# meld_fb2.net
KiCad netlist of a schematic drawn in EAGLE
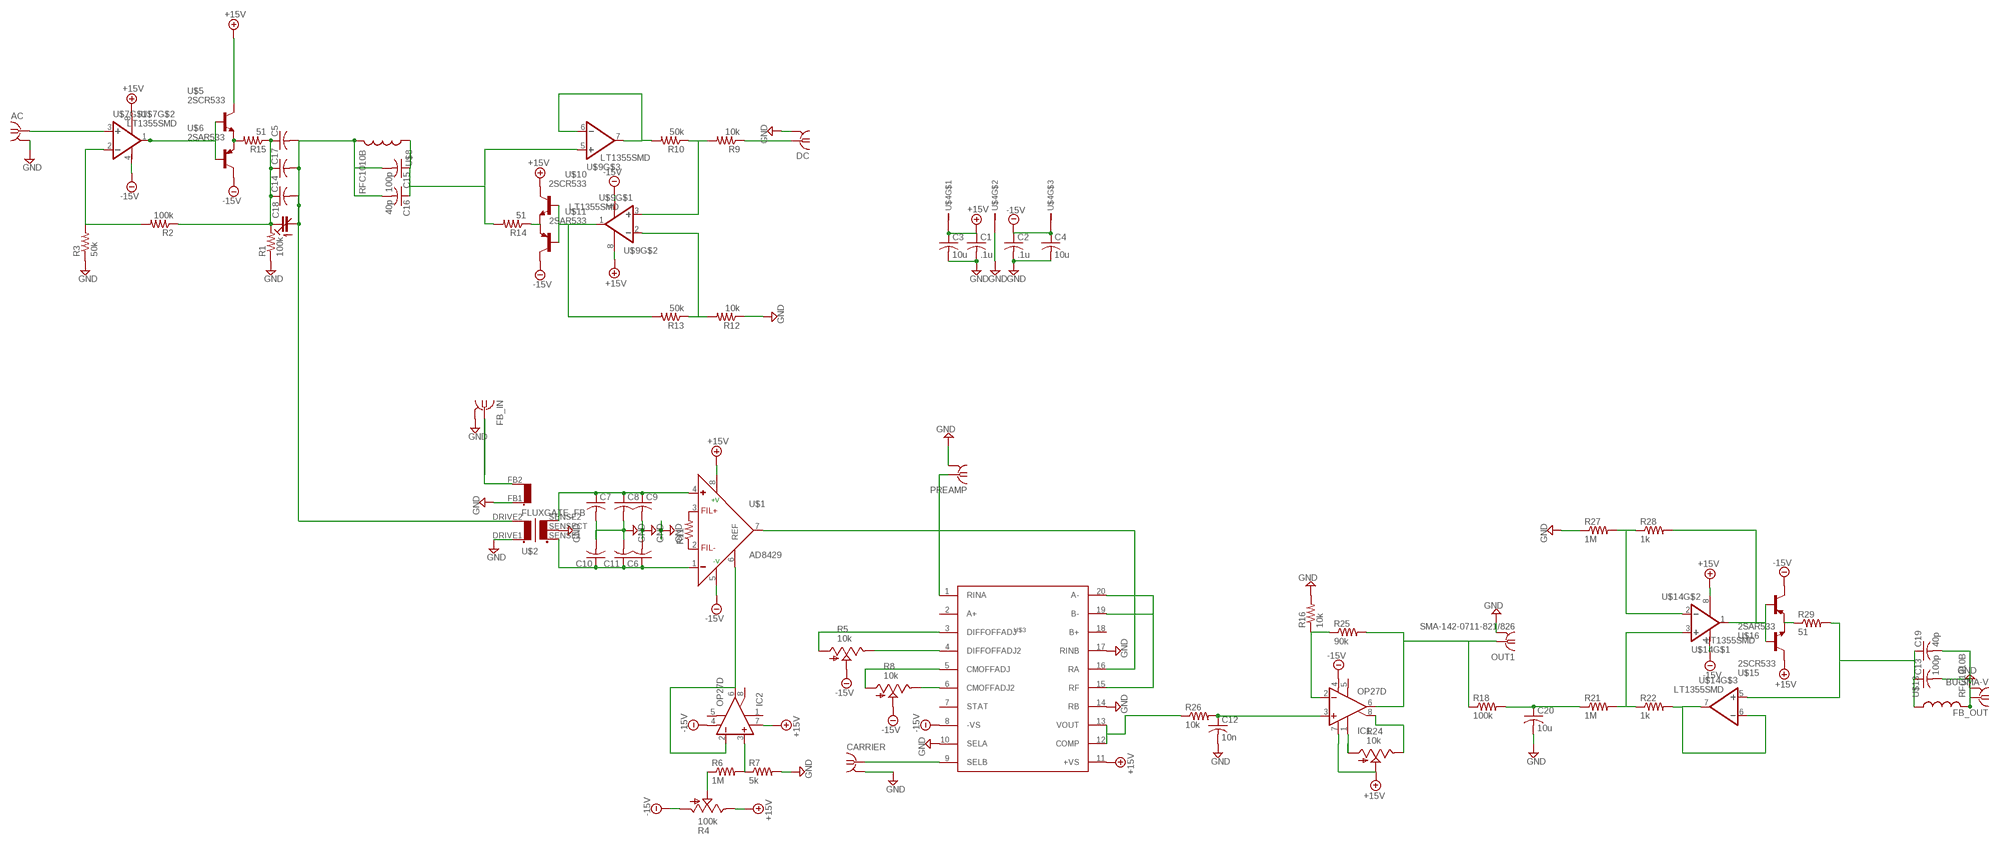
[diagram p0: schematic, sheet 1]

(export (version "E")
  (design (tool "Eeschema 10.0.6"))
  (components
    (comp (ref "AC")
      (value "SMA-142-0711-821/826")
      (footprint "eagle-import:J502-ND-142-0711-821_826")
      (fields (field (name "MF") "JOHNSON COMPONENTS") (field (name "MPN") "142-0711-821"))
      (libsource (lib "eagle-import") (part "SMA-142-0711-821/826"))
    )
    (comp (ref "C1")
      (value ".1u")
      (footprint "eagle-import:C1206")
      (libsource (lib "eagle-import") (part "C-USC1206"))
    )
    (comp (ref "C2")
      (value ".1u")
      (footprint "eagle-import:C1206")
      (libsource (lib "eagle-import") (part "C-USC1206"))
    )
    (comp (ref "C3")
      (value "10u")
      (footprint "eagle-import:C1206")
      (libsource (lib "eagle-import") (part "C-USC1206"))
    )
    (comp (ref "C4")
      (value "10u")
      (footprint "eagle-import:C1206")
      (libsource (lib "eagle-import") (part "C-USC1206"))
    )
    (comp (ref "C5")
      (value "C-USC0805")
      (footprint "eagle-import:C0805")
      (libsource (lib "eagle-import") (part "C-USC0805"))
    )
    (comp (ref "C6")
      (value "C-USC0805")
      (footprint "eagle-import:C0805")
      (libsource (lib "eagle-import") (part "C-USC0805"))
    )
    (comp (ref "C7")
      (value "C-USC0805")
      (footprint "eagle-import:C0805")
      (libsource (lib "eagle-import") (part "C-USC0805"))
    )
    (comp (ref "C8")
      (value "C-USC0805")
      (footprint "eagle-import:C0805")
      (libsource (lib "eagle-import") (part "C-USC0805"))
    )
    (comp (ref "C9")
      (value "C-USC0805")
      (footprint "eagle-import:C0805")
      (libsource (lib "eagle-import") (part "C-USC0805"))
    )
    (comp (ref "C10")
      (value "C-USC0805")
      (footprint "eagle-import:C0805")
      (libsource (lib "eagle-import") (part "C-USC0805"))
    )
    (comp (ref "C11")
      (value "C-USC0805")
      (footprint "eagle-import:C0805")
      (libsource (lib "eagle-import") (part "C-USC0805"))
    )
    (comp (ref "C12")
      (value "10n")
      (footprint "eagle-import:C0805")
      (libsource (lib "eagle-import") (part "C-USC0805"))
    )
    (comp (ref "C13")
      (value "100p")
      (footprint "eagle-import:C0805")
      (libsource (lib "eagle-import") (part "C-USC0805"))
    )
    (comp (ref "C14")
      (value "C-USC0805")
      (footprint "eagle-import:C0805")
      (libsource (lib "eagle-import") (part "C-USC0805"))
    )
    (comp (ref "C15")
      (value "100p")
      (footprint "eagle-import:C0805")
      (libsource (lib "eagle-import") (part "C-USC0805"))
    )
    (comp (ref "C16")
      (value "40p")
      (footprint "eagle-import:C0805")
      (libsource (lib "eagle-import") (part "C-USC0805"))
    )
    (comp (ref "C17")
      (value "C-USC0805")
      (footprint "eagle-import:C0805")
      (libsource (lib "eagle-import") (part "C-USC0805"))
    )
    (comp (ref "C18")
      (value "C-TRIMM")
      (footprint "eagle-import:SGC3S")
      (libsource (lib "eagle-import") (part "C-TRIMM"))
    )
    (comp (ref "C19")
      (value "40p")
      (footprint "eagle-import:C0805")
      (libsource (lib "eagle-import") (part "C-USC0805"))
    )
    (comp (ref "C20")
      (value "10u")
      (footprint "eagle-import:C1206")
      (libsource (lib "eagle-import") (part "C-USC1206"))
    )
    (comp (ref "CARRIER")
      (value "SMA-142-0711-821/826")
      (footprint "eagle-import:J502-ND-142-0711-821_826")
      (fields (field (name "MF") "JOHNSON COMPONENTS") (field (name "MPN") "142-0711-821"))
      (libsource (lib "eagle-import") (part "SMA-142-0711-821/826"))
    )
    (comp (ref "DC")
      (value "SMA-142-0711-821/826")
      (footprint "eagle-import:J502-ND-142-0711-821_826")
      (fields (field (name "MF") "JOHNSON COMPONENTS") (field (name "MPN") "142-0711-821"))
      (libsource (lib "eagle-import") (part "SMA-142-0711-821/826"))
    )
    (comp (ref "FB_IN")
      (value "SMA-142-0711-821/826")
      (footprint "eagle-import:J502-ND-142-0711-821_826")
      (fields (field (name "MF") "JOHNSON COMPONENTS") (field (name "MPN") "142-0711-821"))
      (libsource (lib "eagle-import") (part "SMA-142-0711-821/826"))
    )
    (comp (ref "FB_OUT")
      (value "BU-SMA-V")
      (footprint "eagle-import:BU-SMA-V")
      (libsource (lib "eagle-import") (part "BU-SMA-V"))
    )
    (comp (ref "IC1")
      (value "OP27D")
      (footprint "eagle-import:SO08")
      (libsource (lib "eagle-import") (part "OP27D"))
    )
    (comp (ref "IC2")
      (value "OP27D")
      (footprint "eagle-import:SO08")
      (libsource (lib "eagle-import") (part "OP27D"))
    )
    (comp (ref "OUT1")
      (value "SMA-142-0711-821/826")
      (footprint "eagle-import:J502-ND-142-0711-821_826")
      (fields (field (name "MF") "JOHNSON COMPONENTS") (field (name "MPN") "142-0711-821"))
      (libsource (lib "eagle-import") (part "SMA-142-0711-821/826"))
    )
    (comp (ref "PREAMP")
      (value "SMA-142-0711-821/826")
      (footprint "eagle-import:J502-ND-142-0711-821_826")
      (fields (field (name "MF") "JOHNSON COMPONENTS") (field (name "MPN") "142-0711-821"))
      (libsource (lib "eagle-import") (part "SMA-142-0711-821/826"))
    )
    (comp (ref "R1")
      (value "100k")
      (footprint "eagle-import:R0805")
      (libsource (lib "eagle-import") (part "R-US_R0805"))
    )
    (comp (ref "R2")
      (value "100k")
      (footprint "eagle-import:R0805")
      (libsource (lib "eagle-import") (part "R-US_R0805"))
    )
    (comp (ref "R3")
      (value "50k")
      (footprint "eagle-import:R0805")
      (libsource (lib "eagle-import") (part "R-US_R0805"))
    )
    (comp (ref "R4")
      (value "100k")
      (footprint "eagle-import:B64Y")
      (libsource (lib "eagle-import") (part "TRIM_US-B64Y"))
    )
    (comp (ref "R5")
      (value "10k")
      (footprint "eagle-import:B64Y")
      (libsource (lib "eagle-import") (part "TRIM_US-B64Y"))
    )
    (comp (ref "R6")
      (value "1M")
      (footprint "eagle-import:R0805")
      (libsource (lib "eagle-import") (part "R-US_R0805"))
    )
    (comp (ref "R7")
      (value "5k")
      (footprint "eagle-import:R0805")
      (libsource (lib "eagle-import") (part "R-US_R0805"))
    )
    (comp (ref "R8")
      (value "10k")
      (footprint "eagle-import:B64Y")
      (libsource (lib "eagle-import") (part "TRIM_US-B64Y"))
    )
    (comp (ref "R9")
      (value "10k")
      (footprint "eagle-import:R0805")
      (libsource (lib "eagle-import") (part "R-US_R0805"))
    )
    (comp (ref "R10")
      (value "50k")
      (footprint "eagle-import:R0805")
      (libsource (lib "eagle-import") (part "R-US_R0805"))
    )
    (comp (ref "R11")
      (value "R-US_R0805")
      (footprint "eagle-import:R0805")
      (libsource (lib "eagle-import") (part "R-US_R0805"))
    )
    (comp (ref "R12")
      (value "10k")
      (footprint "eagle-import:R0805")
      (libsource (lib "eagle-import") (part "R-US_R0805"))
    )
    (comp (ref "R13")
      (value "50k")
      (footprint "eagle-import:R0805")
      (libsource (lib "eagle-import") (part "R-US_R0805"))
    )
    (comp (ref "R14")
      (value "51")
      (footprint "eagle-import:R2512")
      (libsource (lib "eagle-import") (part "R-US_R2512"))
    )
    (comp (ref "R15")
      (value "51")
      (footprint "eagle-import:R2512")
      (libsource (lib "eagle-import") (part "R-US_R2512"))
    )
    (comp (ref "R16")
      (value "10k")
      (footprint "eagle-import:R0805")
      (libsource (lib "eagle-import") (part "resistor_R-US_R0805"))
    )
    (comp (ref "R18")
      (value "100k")
      (footprint "eagle-import:R0805")
      (libsource (lib "eagle-import") (part "resistor_R-US_R0805"))
    )
    (comp (ref "R21")
      (value "1M")
      (footprint "eagle-import:R0805")
      (libsource (lib "eagle-import") (part "R-US_R0805"))
    )
    (comp (ref "R22")
      (value "1k")
      (footprint "eagle-import:R0805")
      (libsource (lib "eagle-import") (part "R-US_R0805"))
    )
    (comp (ref "R24")
      (value "10k")
      (footprint "eagle-import:B64Y")
      (libsource (lib "eagle-import") (part "TRIM_US-B64Y"))
    )
    (comp (ref "R25")
      (value "90k")
      (footprint "eagle-import:R0805")
      (libsource (lib "eagle-import") (part "resistor_R-US_R0805"))
    )
    (comp (ref "R26")
      (value "10k")
      (footprint "eagle-import:R0805")
      (libsource (lib "eagle-import") (part "resistor_R-US_R0805"))
    )
    (comp (ref "R27")
      (value "1M")
      (footprint "eagle-import:R0805")
      (libsource (lib "eagle-import") (part "R-US_R0805"))
    )
    (comp (ref "R28")
      (value "1k")
      (footprint "eagle-import:R0805")
      (libsource (lib "eagle-import") (part "R-US_R0805"))
    )
    (comp (ref "R29")
      (value "51")
      (footprint "eagle-import:R2512")
      (libsource (lib "eagle-import") (part "R-US_R2512"))
    )
    (comp (ref "U$1")
      (value "AD8429")
      (footprint "eagle-import:SO8")
      (libsource (lib "eagle-import") (part "AD8428"))
    )
    (comp (ref "U$2")
      (value "FLUXGATE_FB")
      (footprint "eagle-import:PARA_FB")
      (libsource (lib "eagle-import") (part "FLUXGATE_FB"))
    )
    (comp (ref "U$3")
      (value "AD630")
      (footprint "eagle-import:SOIC20R")
      (libsource (lib "eagle-import") (part "AD630"))
    )
    (comp (ref "U$4")
      (value "B3B-AM")
      (footprint "eagle-import:B3B-AM")
      (libsource (lib "eagle-import") (part "B3B-AM"))
    )
    (comp (ref "U$5")
      (value "2SCR533")
      (footprint "eagle-import:SOT89-BCE")
      (libsource (lib "eagle-import") (part "2SCR533"))
    )
    (comp (ref "U$6")
      (value "2SAR533")
      (footprint "eagle-import:SOT89-BCE")
      (libsource (lib "eagle-import") (part "2SAR533"))
    )
    (comp (ref "U$7")
      (value "LT1355SMD")
      (footprint "eagle-import:SOIC8")
      (libsource (lib "eagle-import") (part "LT1355SMD"))
    )
    (comp (ref "U$8")
      (value "RFC1010B")
      (footprint "eagle-import:186KE")
      (libsource (lib "eagle-import") (part "RFC1010B"))
    )
    (comp (ref "U$9")
      (value "LT1355SMD")
      (footprint "eagle-import:SOIC8")
      (libsource (lib "eagle-import") (part "LT1355SMD"))
    )
    (comp (ref "U$10")
      (value "2SCR533")
      (footprint "eagle-import:SOT89-BCE")
      (libsource (lib "eagle-import") (part "2SCR533"))
    )
    (comp (ref "U$11")
      (value "2SAR533")
      (footprint "eagle-import:SOT89-BCE")
      (libsource (lib "eagle-import") (part "2SAR533"))
    )
    (comp (ref "U$13")
      (value "RFC1010B")
      (footprint "eagle-import:186KE")
      (libsource (lib "eagle-import") (part "RFC1010B"))
    )
    (comp (ref "U$14")
      (value "LT1355SMD")
      (footprint "eagle-import:SOIC8")
      (libsource (lib "eagle-import") (part "LT1355SMD"))
    )
    (comp (ref "U$15")
      (value "2SCR533")
      (footprint "eagle-import:SOT89-BCE")
      (libsource (lib "eagle-import") (part "2SCR533"))
    )
    (comp (ref "U$16")
      (value "2SAR533")
      (footprint "eagle-import:SOT89-BCE")
      (libsource (lib "eagle-import") (part "2SAR533"))
    )
  )
  (nets
    (net (code "1") (name "+15V") (class "Default")
      (node (ref "C1") (pin "1") (pinfunction "1_1") (pintype "passive"))
      (node (ref "C3") (pin "1") (pinfunction "1_1") (pintype "passive"))
      (node (ref "IC1") (pin "7") (pinfunction "V+_7") (pintype "power_in"))
      (node (ref "IC2") (pin "7") (pinfunction "V+_7") (pintype "power_in"))
      (node (ref "R24") (pin "S") (pinfunction "S_S") (pintype "passive"))
      (node (ref "R4") (pin "E") (pinfunction "E_E") (pintype "passive"))
      (node (ref "U$1") (pin "8") (pinfunction "+V_8") (pintype "power_in"))
      (node (ref "U$10") (pin "C") (pinfunction "C_C") (pintype "passive"))
      (node (ref "U$14") (pin "8") (pinfunction "V+_8") (pintype "power_in"))
      (node (ref "U$15") (pin "C") (pinfunction "C_C") (pintype "passive"))
      (node (ref "U$3") (pin "11") (pinfunction "+VS_11") (pintype "bidirectional"))
      (node (ref "U$4") (pin "1") (pinfunction "1_1") (pintype "passive"))
      (node (ref "U$5") (pin "C") (pinfunction "C_C") (pintype "passive"))
      (node (ref "U$7") (pin "8") (pinfunction "V+_8") (pintype "power_in"))
      (node (ref "U$9") (pin "8") (pinfunction "V+_8") (pintype "power_in"))
    )
    (net (code "2") (name "-15V") (class "Default")
      (node (ref "C2") (pin "1") (pinfunction "1_1") (pintype "passive"))
      (node (ref "C4") (pin "1") (pinfunction "1_1") (pintype "passive"))
      (node (ref "IC1") (pin "4") (pinfunction "V-_4") (pintype "power_in"))
      (node (ref "IC2") (pin "4") (pinfunction "V-_4") (pintype "power_in"))
      (node (ref "R4") (pin "A") (pinfunction "A_A") (pintype "passive"))
      (node (ref "R5") (pin "S") (pinfunction "S_S") (pintype "passive"))
      (node (ref "R8") (pin "S") (pinfunction "S_S") (pintype "passive"))
      (node (ref "U$1") (pin "5") (pinfunction "-V_5") (pintype "power_in"))
      (node (ref "U$11") (pin "C") (pinfunction "C_C") (pintype "passive"))
      (node (ref "U$14") (pin "4") (pinfunction "V-_4") (pintype "power_in"))
      (node (ref "U$16") (pin "C") (pinfunction "C_C") (pintype "passive"))
      (node (ref "U$3") (pin "8") (pinfunction "-VS_8") (pintype "bidirectional"))
      (node (ref "U$4") (pin "3") (pinfunction "1_3") (pintype "passive"))
      (node (ref "U$6") (pin "C") (pinfunction "C_C") (pintype "passive"))
      (node (ref "U$7") (pin "4") (pinfunction "V-_4") (pintype "power_in"))
      (node (ref "U$9") (pin "4") (pinfunction "V-_4") (pintype "power_in"))
    )
    (net (code "3") (name "GND") (class "Default")
      (node (ref "AC") (pin "G@1") (pinfunction "2_G@1") (pintype "passive"))
      (node (ref "AC") (pin "G@2") (pinfunction "2_G@2") (pintype "passive"))
      (node (ref "AC") (pin "G@3") (pinfunction "2_G@3") (pintype "passive"))
      (node (ref "AC") (pin "G@4") (pinfunction "2_G@4") (pintype "passive"))
      (node (ref "C1") (pin "2") (pinfunction "2_2") (pintype "passive"))
      (node (ref "C10") (pin "2") (pinfunction "2_2") (pintype "passive"))
      (node (ref "C11") (pin "2") (pinfunction "2_2") (pintype "passive"))
      (node (ref "C12") (pin "2") (pinfunction "2_2") (pintype "passive"))
      (node (ref "C2") (pin "2") (pinfunction "2_2") (pintype "passive"))
      (node (ref "C20") (pin "2") (pinfunction "2_2") (pintype "passive"))
      (node (ref "C3") (pin "2") (pinfunction "2_2") (pintype "passive"))
      (node (ref "C4") (pin "2") (pinfunction "2_2") (pintype "passive"))
      (node (ref "C6") (pin "2") (pinfunction "2_2") (pintype "passive"))
      (node (ref "C7") (pin "2") (pinfunction "2_2") (pintype "passive"))
      (node (ref "C8") (pin "2") (pinfunction "2_2") (pintype "passive"))
      (node (ref "C9") (pin "2") (pinfunction "2_2") (pintype "passive"))
      (node (ref "CARRIER") (pin "G@1") (pinfunction "2_G@1") (pintype "passive"))
      (node (ref "CARRIER") (pin "G@2") (pinfunction "2_G@2") (pintype "passive"))
      (node (ref "CARRIER") (pin "G@3") (pinfunction "2_G@3") (pintype "passive"))
      (node (ref "CARRIER") (pin "G@4") (pinfunction "2_G@4") (pintype "passive"))
      (node (ref "DC") (pin "G@1") (pinfunction "2_G@1") (pintype "passive"))
      (node (ref "DC") (pin "G@2") (pinfunction "2_G@2") (pintype "passive"))
      (node (ref "DC") (pin "G@3") (pinfunction "2_G@3") (pintype "passive"))
      (node (ref "DC") (pin "G@4") (pinfunction "2_G@4") (pintype "passive"))
      (node (ref "FB_IN") (pin "G@1") (pinfunction "2_G@1") (pintype "passive"))
      (node (ref "FB_IN") (pin "G@2") (pinfunction "2_G@2") (pintype "passive"))
      (node (ref "FB_IN") (pin "G@3") (pinfunction "2_G@3") (pintype "passive"))
      (node (ref "FB_IN") (pin "G@4") (pinfunction "2_G@4") (pintype "passive"))
      (node (ref "FB_OUT") (pin "2") (pinfunction "2_2") (pintype "passive"))
      (node (ref "FB_OUT") (pin "3") (pinfunction "2_3") (pintype "passive"))
      (node (ref "FB_OUT") (pin "4") (pinfunction "2_4") (pintype "passive"))
      (node (ref "FB_OUT") (pin "5") (pinfunction "2_5") (pintype "passive"))
      (node (ref "OUT1") (pin "G@1") (pinfunction "2_G@1") (pintype "passive"))
      (node (ref "OUT1") (pin "G@2") (pinfunction "2_G@2") (pintype "passive"))
      (node (ref "OUT1") (pin "G@3") (pinfunction "2_G@3") (pintype "passive"))
      (node (ref "OUT1") (pin "G@4") (pinfunction "2_G@4") (pintype "passive"))
      (node (ref "PREAMP") (pin "G@1") (pinfunction "2_G@1") (pintype "passive"))
      (node (ref "PREAMP") (pin "G@2") (pinfunction "2_G@2") (pintype "passive"))
      (node (ref "PREAMP") (pin "G@3") (pinfunction "2_G@3") (pintype "passive"))
      (node (ref "PREAMP") (pin "G@4") (pinfunction "2_G@4") (pintype "passive"))
      (node (ref "R1") (pin "1") (pinfunction "1_1") (pintype "passive"))
      (node (ref "R12") (pin "1") (pinfunction "1_1") (pintype "passive"))
      (node (ref "R16") (pin "2") (pinfunction "2_2") (pintype "passive"))
      (node (ref "R27") (pin "1") (pinfunction "1_1") (pintype "passive"))
      (node (ref "R3") (pin "1") (pinfunction "1_1") (pintype "passive"))
      (node (ref "R7") (pin "2") (pinfunction "2_2") (pintype "passive"))
      (node (ref "U$2") (pin "DRIVE1") (pinfunction "1_DRIVE1") (pintype "passive"))
      (node (ref "U$2") (pin "FB1") (pinfunction "6_FB1") (pintype "passive"))
      (node (ref "U$2") (pin "SENSECT") (pinfunction "4_SENSECT") (pintype "passive"))
      (node (ref "U$3") (pin "10") (pinfunction "SELA_10") (pintype "bidirectional"))
      (node (ref "U$3") (pin "14") (pinfunction "RB_14") (pintype "bidirectional"))
      (node (ref "U$3") (pin "17") (pinfunction "RINB_17") (pintype "bidirectional"))
      (node (ref "U$4") (pin "2") (pinfunction "1_2") (pintype "passive"))
    )
    (net (code "4") (name "Net-(C18-A)") (class "Default")
      (node (ref "C14") (pin "2") (pinfunction "2_2") (pintype "passive"))
      (node (ref "C15") (pin "2") (pinfunction "2_2") (pintype "passive"))
      (node (ref "C16") (pin "2") (pinfunction "2_2") (pintype "passive"))
      (node (ref "C17") (pin "2") (pinfunction "2_2") (pintype "passive"))
      (node (ref "C18") (pin "P$1") (pinfunction "A_P$1") (pintype "passive"))
      (node (ref "C5") (pin "2") (pinfunction "2_2") (pintype "passive"))
      (node (ref "U$2") (pin "DRIVE2") (pinfunction "2_DRIVE2") (pintype "passive"))
      (node (ref "U$8") (pin "P$2") (pinfunction "2_P$2") (pintype "passive"))
    )
    (net (code "5") (name "Net-(C18-E)") (class "Default")
      (node (ref "C14") (pin "1") (pinfunction "1_1") (pintype "passive"))
      (node (ref "C17") (pin "1") (pinfunction "1_1") (pintype "passive"))
      (node (ref "C18") (pin "P$2") (pinfunction "E_P$2") (pintype "passive"))
      (node (ref "C5") (pin "1") (pinfunction "1_1") (pintype "passive"))
      (node (ref "R1") (pin "2") (pinfunction "2_2") (pintype "passive"))
      (node (ref "R15") (pin "1") (pinfunction "1_1") (pintype "passive"))
      (node (ref "R2") (pin "1") (pinfunction "1_1") (pintype "passive"))
    )
    (net (code "6") (name "Net-(C20-Pad1)") (class "Default")
      (node (ref "C20") (pin "1") (pinfunction "1_1") (pintype "passive"))
      (node (ref "R18") (pin "2") (pinfunction "2_2") (pintype "passive"))
      (node (ref "R21") (pin "1") (pinfunction "1_1") (pintype "passive"))
    )
    (net (code "7") (name "Net-(DC-Pad1)") (class "Default")
      (node (ref "DC") (pin "1") (pinfunction "1_1") (pintype "passive"))
      (node (ref "R9") (pin "1") (pinfunction "1_1") (pintype "passive"))
    )
    (net (code "8") (name "Net-(IC1-+IN)") (class "Default")
      (node (ref "C12") (pin "1") (pinfunction "1_1") (pintype "passive"))
      (node (ref "IC1") (pin "3") (pinfunction "+IN_3") (pintype "input"))
      (node (ref "R26") (pin "2") (pinfunction "2_2") (pintype "passive"))
    )
    (net (code "9") (name "Net-(IC1--IN)") (class "Default")
      (node (ref "IC1") (pin "2") (pinfunction "-IN_2") (pintype "input"))
      (node (ref "R16") (pin "1") (pinfunction "1_1") (pintype "passive"))
      (node (ref "R25") (pin "1") (pinfunction "1_1") (pintype "passive"))
    )
    (net (code "10") (name "Net-(IC1-ON1)") (class "Default")
      (node (ref "IC1") (pin "1") (pinfunction "ON1_1") (pintype "passive"))
      (node (ref "R24") (pin "A") (pinfunction "A_A") (pintype "passive"))
    )
    (net (code "11") (name "Net-(IC1-ON2)") (class "Default")
      (node (ref "IC1") (pin "8") (pinfunction "ON2_8") (pintype "passive"))
      (node (ref "R24") (pin "E") (pinfunction "E_E") (pintype "passive"))
    )
    (net (code "12") (name "Net-(IC1-OUT)") (class "Default")
      (node (ref "IC1") (pin "6") (pinfunction "OUT_6") (pintype "output"))
      (node (ref "OUT1") (pin "1") (pinfunction "1_1") (pintype "passive"))
      (node (ref "R18") (pin "1") (pinfunction "1_1") (pintype "passive"))
      (node (ref "R25") (pin "2") (pinfunction "2_2") (pintype "passive"))
    )
    (net (code "13") (name "Net-(IC2-+IN)") (class "Default")
      (node (ref "IC2") (pin "3") (pinfunction "+IN_3") (pintype "input"))
      (node (ref "R6") (pin "2") (pinfunction "2_2") (pintype "passive"))
      (node (ref "R7") (pin "1") (pinfunction "1_1") (pintype "passive"))
    )
    (net (code "14") (name "Net-(IC2--IN)") (class "Default")
      (node (ref "IC2") (pin "2") (pinfunction "-IN_2") (pintype "input"))
      (node (ref "IC2") (pin "6") (pinfunction "OUT_6") (pintype "output"))
      (node (ref "U$1") (pin "6") (pinfunction "REF_6") (pintype "passive"))
    )
    (net (code "15") (name "Net-(R4-PadS)") (class "Default")
      (node (ref "R4") (pin "S") (pinfunction "S_S") (pintype "passive"))
      (node (ref "R6") (pin "1") (pinfunction "1_1") (pintype "passive"))
    )
    (net (code "16") (name "Net-(R14-Pad1)") (class "Default")
      (node (ref "R14") (pin "1") (pinfunction "1_1") (pintype "passive"))
      (node (ref "U$10") (pin "E") (pinfunction "E_E") (pintype "passive"))
      (node (ref "U$11") (pin "E") (pinfunction "E_E") (pintype "passive"))
    )
    (net (code "17") (name "Net-(R15-Pad2)") (class "Default")
      (node (ref "R15") (pin "2") (pinfunction "2_2") (pintype "passive"))
      (node (ref "U$5") (pin "E") (pinfunction "E_E") (pintype "passive"))
      (node (ref "U$6") (pin "E") (pinfunction "E_E") (pintype "passive"))
    )
    (net (code "18") (name "Net-(R29-Pad1)") (class "Default")
      (node (ref "R29") (pin "1") (pinfunction "1_1") (pintype "passive"))
      (node (ref "U$15") (pin "E") (pinfunction "E_E") (pintype "passive"))
      (node (ref "U$16") (pin "E") (pinfunction "E_E") (pintype "passive"))
    )
    (net (code "19") (name "Net-(U$1-+)") (class "Default")
      (node (ref "C7") (pin "1") (pinfunction "1_1") (pintype "passive"))
      (node (ref "C8") (pin "1") (pinfunction "1_1") (pintype "passive"))
      (node (ref "C9") (pin "1") (pinfunction "1_1") (pintype "passive"))
      (node (ref "U$1") (pin "4") (pinfunction "+_4") (pintype "input"))
      (node (ref "U$2") (pin "SENSE2") (pinfunction "3_SENSE2") (pintype "passive"))
    )
    (net (code "20") (name "Net-(U$1--)") (class "Default")
      (node (ref "C10") (pin "1") (pinfunction "1_1") (pintype "passive"))
      (node (ref "C11") (pin "1") (pinfunction "1_1") (pintype "passive"))
      (node (ref "C6") (pin "1") (pinfunction "1_1") (pintype "passive"))
      (node (ref "U$1") (pin "1") (pinfunction "-_1") (pintype "input"))
      (node (ref "U$2") (pin "SENSE1") (pinfunction "5_SENSE1") (pintype "passive"))
    )
    (net (code "21") (name "Net-(U$1-FIL+)") (class "Default")
      (node (ref "R11") (pin "2") (pinfunction "2_2") (pintype "passive"))
      (node (ref "U$1") (pin "3") (pinfunction "FIL+_3") (pintype "passive"))
    )
    (net (code "22") (name "Net-(U$1-FIL-)") (class "Default")
      (node (ref "R11") (pin "1") (pinfunction "1_1") (pintype "passive"))
      (node (ref "U$1") (pin "2") (pinfunction "FIL-_2") (pintype "passive"))
    )
    (net (code "23") (name "Net-(U$1-OUT)") (class "Default")
      (node (ref "PREAMP") (pin "1") (pinfunction "1_1") (pintype "passive"))
      (node (ref "U$1") (pin "7") (pinfunction "OUT_7") (pintype "output"))
      (node (ref "U$3") (pin "1") (pinfunction "RINA_1") (pintype "bidirectional"))
      (node (ref "U$3") (pin "16") (pinfunction "RA_16") (pintype "bidirectional"))
    )
    (net (code "24") (name "Net-(U$2-7)") (class "Default")
      (node (ref "FB_IN") (pin "1") (pinfunction "1_1") (pintype "passive"))
      (node (ref "U$2") (pin "FB2") (pinfunction "7_FB2") (pintype "passive"))
    )
    (net (code "25") (name "Net-(U$3-A-)") (class "Default")
      (node (ref "U$3") (pin "15") (pinfunction "RF_15") (pintype "bidirectional"))
      (node (ref "U$3") (pin "19") (pinfunction "B-_19") (pintype "bidirectional"))
      (node (ref "U$3") (pin "20") (pinfunction "A-_20") (pintype "bidirectional"))
    )
    (net (code "26") (name "Net-(U$3-CMOFFADJ)") (class "Default")
      (node (ref "R8") (pin "A") (pinfunction "A_A") (pintype "passive"))
      (node (ref "U$3") (pin "5") (pinfunction "CMOFFADJ_5") (pintype "bidirectional"))
    )
    (net (code "27") (name "Net-(U$3-CMOFFADJ2)") (class "Default")
      (node (ref "R8") (pin "E") (pinfunction "E_E") (pintype "passive"))
      (node (ref "U$3") (pin "6") (pinfunction "CMOFFADJ2_6") (pintype "bidirectional"))
    )
    (net (code "28") (name "Net-(U$3-COMP)") (class "Default")
      (node (ref "R26") (pin "1") (pinfunction "1_1") (pintype "passive"))
      (node (ref "U$3") (pin "12") (pinfunction "COMP_12") (pintype "bidirectional"))
      (node (ref "U$3") (pin "13") (pinfunction "VOUT_13") (pintype "bidirectional"))
    )
    (net (code "29") (name "Net-(U$3-DIFFOFFADJ)") (class "Default")
      (node (ref "R5") (pin "A") (pinfunction "A_A") (pintype "passive"))
      (node (ref "U$3") (pin "3") (pinfunction "DIFFOFFADJ_3") (pintype "bidirectional"))
    )
    (net (code "30") (name "Net-(U$3-DIFFOFFADJ2)") (class "Default")
      (node (ref "R5") (pin "E") (pinfunction "E_E") (pintype "passive"))
      (node (ref "U$3") (pin "4") (pinfunction "DIFFOFFADJ2_4") (pintype "bidirectional"))
    )
    (net (code "31") (name "Net-(U$3-SELB)") (class "Default")
      (node (ref "CARRIER") (pin "1") (pinfunction "1_1") (pintype "passive"))
      (node (ref "U$3") (pin "9") (pinfunction "SELB_9") (pintype "bidirectional"))
    )
    (net (code "32") (name "Net-(U$7A-+IN)") (class "Default")
      (node (ref "AC") (pin "1") (pinfunction "1_1") (pintype "passive"))
      (node (ref "U$7") (pin "3") (pinfunction "+IN_3") (pintype "input"))
    )
    (net (code "33") (name "Net-(U$7A--IN)") (class "Default")
      (node (ref "R2") (pin "2") (pinfunction "2_2") (pintype "passive"))
      (node (ref "R3") (pin "2") (pinfunction "2_2") (pintype "passive"))
      (node (ref "U$7") (pin "2") (pinfunction "-IN_2") (pintype "input"))
    )
    (net (code "34") (name "Net-(U$7A-OUT)") (class "Default")
      (node (ref "U$5") (pin "B") (pinfunction "B_B") (pintype "passive"))
      (node (ref "U$6") (pin "B") (pinfunction "B_B") (pintype "passive"))
      (node (ref "U$7") (pin "1") (pinfunction "OUT_1") (pintype "output"))
    )
    (net (code "35") (name "Net-(U$8-1)") (class "Default")
      (node (ref "C15") (pin "1") (pinfunction "1_1") (pintype "passive"))
      (node (ref "C16") (pin "1") (pinfunction "1_1") (pintype "passive"))
      (node (ref "R14") (pin "2") (pinfunction "2_2") (pintype "passive"))
      (node (ref "U$8") (pin "P$1") (pinfunction "1_P$1") (pintype "passive"))
      (node (ref "U$9") (pin "5") (pinfunction "+IN_5") (pintype "input"))
    )
    (net (code "36") (name "Net-(U$9A-+IN)") (class "Default")
      (node (ref "R10") (pin "1") (pinfunction "1_1") (pintype "passive"))
      (node (ref "R9") (pin "2") (pinfunction "2_2") (pintype "passive"))
      (node (ref "U$9") (pin "3") (pinfunction "+IN_3") (pintype "input"))
    )
    (net (code "37") (name "Net-(U$9A--IN)") (class "Default")
      (node (ref "R12") (pin "2") (pinfunction "2_2") (pintype "passive"))
      (node (ref "R13") (pin "1") (pinfunction "1_1") (pintype "passive"))
      (node (ref "U$9") (pin "2") (pinfunction "-IN_2") (pintype "input"))
    )
    (net (code "38") (name "Net-(U$9A-OUT)") (class "Default")
      (node (ref "R13") (pin "2") (pinfunction "2_2") (pintype "passive"))
      (node (ref "U$10") (pin "B") (pinfunction "B_B") (pintype "passive"))
      (node (ref "U$11") (pin "B") (pinfunction "B_B") (pintype "passive"))
      (node (ref "U$9") (pin "1") (pinfunction "OUT_1") (pintype "output"))
    )
    (net (code "39") (name "Net-(U$9C--IN)") (class "Default")
      (node (ref "R10") (pin "2") (pinfunction "2_2") (pintype "passive"))
      (node (ref "U$9") (pin "6") (pinfunction "-IN_6") (pintype "input"))
      (node (ref "U$9") (pin "7") (pinfunction "OUT_7") (pintype "output"))
    )
    (net (code "40") (name "Net-(U$13-1)") (class "Default")
      (node (ref "C13") (pin "1") (pinfunction "1_1") (pintype "passive"))
      (node (ref "C19") (pin "1") (pinfunction "1_1") (pintype "passive"))
      (node (ref "R29") (pin "2") (pinfunction "2_2") (pintype "passive"))
      (node (ref "U$13") (pin "P$1") (pinfunction "1_P$1") (pintype "passive"))
      (node (ref "U$14") (pin "5") (pinfunction "+IN_5") (pintype "input"))
    )
    (net (code "41") (name "Net-(U$13-2)") (class "Default")
      (node (ref "C13") (pin "2") (pinfunction "2_2") (pintype "passive"))
      (node (ref "C19") (pin "2") (pinfunction "2_2") (pintype "passive"))
      (node (ref "FB_OUT") (pin "1") (pinfunction "1_1") (pintype "passive"))
      (node (ref "U$13") (pin "P$2") (pinfunction "2_P$2") (pintype "passive"))
    )
    (net (code "42") (name "Net-(U$14A-+IN)") (class "Default")
      (node (ref "R21") (pin "2") (pinfunction "2_2") (pintype "passive"))
      (node (ref "R22") (pin "1") (pinfunction "1_1") (pintype "passive"))
      (node (ref "U$14") (pin "3") (pinfunction "+IN_3") (pintype "input"))
    )
    (net (code "43") (name "Net-(U$14A--IN)") (class "Default")
      (node (ref "R27") (pin "2") (pinfunction "2_2") (pintype "passive"))
      (node (ref "R28") (pin "1") (pinfunction "1_1") (pintype "passive"))
      (node (ref "U$14") (pin "2") (pinfunction "-IN_2") (pintype "input"))
    )
    (net (code "44") (name "Net-(U$14A-OUT)") (class "Default")
      (node (ref "R28") (pin "2") (pinfunction "2_2") (pintype "passive"))
      (node (ref "U$14") (pin "1") (pinfunction "OUT_1") (pintype "output"))
      (node (ref "U$15") (pin "B") (pinfunction "B_B") (pintype "passive"))
      (node (ref "U$16") (pin "B") (pinfunction "B_B") (pintype "passive"))
    )
    (net (code "45") (name "Net-(U$14C--IN)") (class "Default")
      (node (ref "R22") (pin "2") (pinfunction "2_2") (pintype "passive"))
      (node (ref "U$14") (pin "6") (pinfunction "-IN_6") (pintype "input"))
      (node (ref "U$14") (pin "7") (pinfunction "OUT_7") (pintype "output"))
    )
    (net (code "46") (name "unconnected-(IC1-OPT-Pad5)") (class "Default")
      (node (ref "IC1") (pin "5") (pinfunction "OPT_5") (pintype "passive"))
    )
    (net (code "47") (name "unconnected-(IC2-ON1-Pad1)") (class "Default")
      (node (ref "IC2") (pin "1") (pinfunction "ON1_1") (pintype "passive"))
    )
    (net (code "48") (name "unconnected-(IC2-ON2-Pad8)") (class "Default")
      (node (ref "IC2") (pin "8") (pinfunction "ON2_8") (pintype "passive"))
    )
    (net (code "49") (name "unconnected-(IC2-OPT-Pad5)") (class "Default")
      (node (ref "IC2") (pin "5") (pinfunction "OPT_5") (pintype "passive"))
    )
    (net (code "50") (name "unconnected-(U$3-A+-Pad2)") (class "Default")
      (node (ref "U$3") (pin "2") (pinfunction "A+_2") (pintype "bidirectional"))
    )
    (net (code "51") (name "unconnected-(U$3-B+-Pad18)") (class "Default")
      (node (ref "U$3") (pin "18") (pinfunction "B+_18") (pintype "bidirectional"))
    )
    (net (code "52") (name "unconnected-(U$3-STAT-Pad7)") (class "Default")
      (node (ref "U$3") (pin "7") (pinfunction "STAT_7") (pintype "bidirectional"))
    )
  )
)
